# LED-Driver-Sheet.net
KiCad netlist of a schematic drawn in Altium Designer
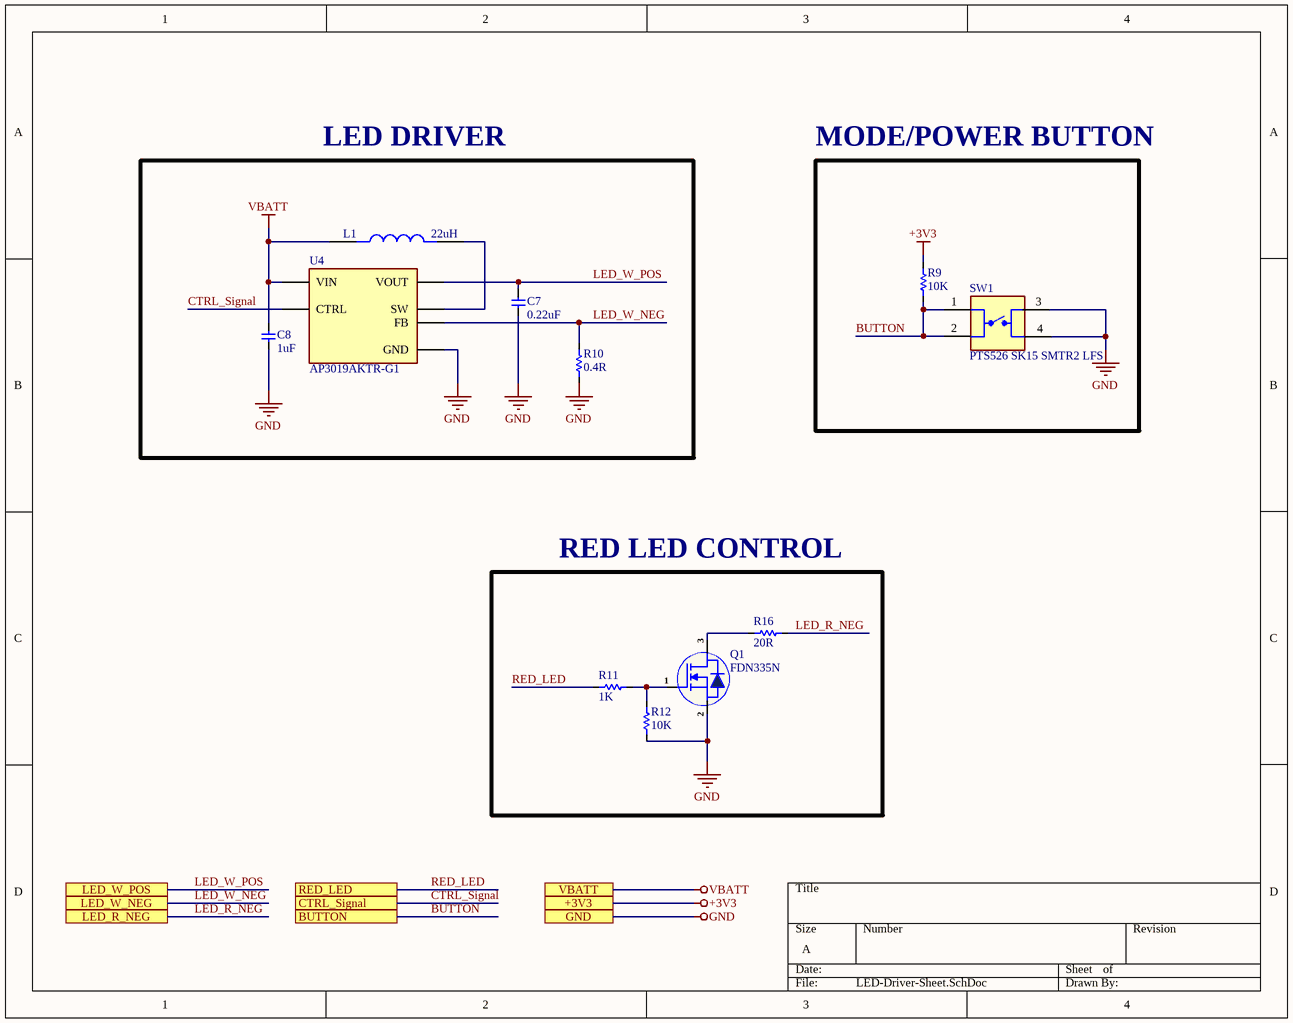
[diagram p0: LED-Driver-Sheet.SchDoc]

(export (version "E")
  (design (tool "Eeschema 10.0.6"))
  (components
    (comp (ref "C7")
      (value "0.22uF")
      (footprint "Cap-0402")
      (description "0.22 µF ±10% 25V Ceramic Capacitor X5R 0402 (1005 Metric)")
      (fields
        (field (name "MANUFACTURER") "YAGEO")
        (field (name "MANUFACTURER PART NUMBER") "CC0402KRX5R8BB224")
      )
      (libsource (lib "LED-Driver-Library") (part "CC0402KRX5R8BB224"))
    )
    (comp (ref "C8")
      (value "1uF")
      (footprint "Cap-0402")
      (description "1 µF ±20% 6.3V Ceramic Capacitor X5R 0201 (0603 Metric)")
      (fields
        (field (name "MANUFACTURER") "Murata Electronics")
        (field (name "MANUFACTURER PART NUMBER") "GRM033R60J105MEA2D")
      )
      (libsource (lib "LED-Driver-Library") (part "GRM033R60J105MEA2D"))
    )
    (comp (ref "L1")
      (value "22uH")
      (footprint "IND_1235AS-H-220M=P3")
      (description "Inductor Power Shielded Wirewound 22uH 20% 100KHz Ferrite 1A 0.306Ohm DCR 1818 T/R")
      (fields
        (field (name "MANUFACTURER") "Murata Electronics")
        (field (name "MANUFACTURER PART NUMBER") "1235AS-H-220M=P3")
      )
      (libsource (lib "LED-Driver-Library") (part "1235AS-H-220M=P3"))
    )
    (comp (ref "Q1")
      (value "FDN335N")
      (footprint "SOT-23")
      (description "SOT-23 MOSFETs ROHS")
      (fields (field (name "MANUFACTURER") "onsemi") (field (name "DIGIKEY PART NUMBER") "FDN335NDKR-ND"))
      (libsource (lib "LED-Driver-Library") (part "FDN335N"))
    )
    (comp (ref "R9")
      (value "10K")
      (footprint "Res-0402")
      (description "10 kOhms ±1% 0.063W, 1/16W Chip Resistor 0402 (1005 Metric) Moisture Resistant Thick Film")
      (fields
        (field (name "MANUFACTURER") "YAGEO")
        (field (name "MANUFACTURER PART NUMBER") "RC0402FR-0710KL")
      )
      (libsource (lib "LED-Driver-Library") (part "RC0603FR-0710KL"))
    )
    (comp (ref "R10")
      (value "0.4R")
      (footprint "Res-1206")
      (fields
        (field (name "MANUFACTURER") "YAGEO")
        (field (name "MANUFACTURER PART NUMBER") "RL1206FR-070R4L")
        (field (name "DIGIKEY PART NUMBER") "311-.4LWDKR-ND")
      )
      (libsource (lib "LED-Driver-Library") (part "RL1206FR-070R4L"))
    )
    (comp (ref "R11")
      (value "1K")
      (footprint "Res-0402")
      (description "1 kOhms ±1% 0.063W, 1/16W Chip Resistor 0402 (1005 Metric) Moisture Resistant Thick Film")
      (fields
        (field (name "MANUFACTURER") "YAGEO")
        (field (name "MANUFACTURER PART NUMBER") "RC0402FR-071KL")
      )
      (libsource (lib "LED-Driver-Library") (part "RC0402FR-071KL"))
    )
    (comp (ref "R12")
      (value "10K")
      (footprint "Res-0402")
      (description "10 kOhms ±1% 0.063W, 1/16W Chip Resistor 0402 (1005 Metric) Moisture Resistant Thick Film")
      (fields
        (field (name "MANUFACTURER") "YAGEO")
        (field (name "MANUFACTURER PART NUMBER") "RC0402FR-0710KL")
      )
      (libsource (lib "LED-Driver-Library") (part "RC0603FR-0710KL"))
    )
    (comp (ref "R16")
      (value "20R")
      (footprint "RESC1005X40N")
      (fields
        (field (name "MANUFACTURER") "Vishay Dale")
        (field (name "MANUFACTURER PART NUMBER") "RCS040220R0FKED")
        (field (name "DIGIKEY PART NUMBER") "541-RCS040220R0FKEDDKR-ND")
      )
      (libsource (lib "LED-Driver-Library") (part "RCS040220R0FKED"))
    )
    (comp (ref "SW1")
      (value "PTS526 SK15 SMTR2 LFS")
      (footprint "PTS525SM15SMTR2LFS")
      (description "Tactile Switch SPST-NO Top Actuated Surface Mount")
      (fields
        (field (name "MANUFACTURER") "TE Connectivity ALCOSWITCH Switches")
        (field (name "MANUFACTURER PART NUMBER") "MCSLPT4644B1PHTR")
      )
      (libsource (lib "LED-Driver-Library") (part "MCSLPT4644B1PHTR"))
    )
    (comp (ref "U4")
      (value "AP3019AKTR-G1")
      (footprint "AP3019AKTR-G1")
      (description "LED Driver IC 1 Output DC DC Regulator Step-Up (Boost) PWM Dimming 550mA (Switch) SOT-23-6")
      (fields
        (field (name "MANUFACTURER") "Diodes Incorporated")
        (field (name "DIGIKEY PART NUMBER") "AP3019AKTR-G1DIDKR-ND")
      )
      (libsource (lib "LED-Driver-Library") (part "AP3019AKTR-G1"))
    )
  )
  (nets
    (net (code "1") (name "+3V3") (class "Default")
      (node (ref "R9") (pin "1") (pinfunction "1_1") (pintype "passive"))
    )
    (net (code "2") (name "/BUTTON") (class "Default")
      (node (ref "R9") (pin "2") (pinfunction "2_2") (pintype "passive"))
      (node (ref "SW1") (pin "1") (pinfunction "1_1") (pintype "passive"))
      (node (ref "SW1") (pin "2") (pinfunction "2_2") (pintype "passive"))
    )
    (net (code "3") (name "/CTRL_Signal") (class "Default")
      (node (ref "U4") (pin "4") (pinfunction "CTRL_4") (pintype "passive"))
    )
    (net (code "4") (name "/LED_R_NEG") (class "Default")
      (node (ref "R16") (pin "2") (pinfunction "2_2") (pintype "passive"))
    )
    (net (code "5") (name "/LED_W_NEG") (class "Default")
      (node (ref "R10") (pin "2") (pinfunction "2_2") (pintype "passive"))
      (node (ref "U4") (pin "3") (pinfunction "FB_3") (pintype "passive"))
    )
    (net (code "6") (name "/LED_W_POS") (class "Default")
      (node (ref "C7") (pin "2") (pinfunction "2_2") (pintype "passive"))
      (node (ref "U4") (pin "5") (pinfunction "VOUT_5") (pintype "passive"))
    )
    (net (code "7") (name "/RED_LED") (class "Default")
      (node (ref "R11") (pin "1") (pinfunction "1_1") (pintype "passive"))
    )
    (net (code "8") (name "GND") (class "Default")
      (node (ref "C7") (pin "1") (pinfunction "1_1") (pintype "passive"))
      (node (ref "C8") (pin "1") (pinfunction "1_1") (pintype "passive"))
      (node (ref "Q1") (pin "2") (pinfunction "S_2") (pintype "passive"))
      (node (ref "R10") (pin "1") (pinfunction "1_1") (pintype "passive"))
      (node (ref "R12") (pin "2") (pinfunction "2_2") (pintype "passive"))
      (node (ref "SW1") (pin "3") (pinfunction "3_3") (pintype "passive"))
      (node (ref "SW1") (pin "4") (pinfunction "4_4") (pintype "passive"))
      (node (ref "U4") (pin "2") (pinfunction "GND_2") (pintype "passive"))
    )
    (net (code "9") (name "Net-(Q1-D)") (class "Default")
      (node (ref "Q1") (pin "3") (pinfunction "D_3") (pintype "passive"))
      (node (ref "R16") (pin "1") (pinfunction "1_1") (pintype "passive"))
    )
    (net (code "10") (name "Net-(Q1-G)") (class "Default")
      (node (ref "Q1") (pin "1") (pinfunction "G_1") (pintype "passive"))
      (node (ref "R11") (pin "2") (pinfunction "2_2") (pintype "passive"))
      (node (ref "R12") (pin "1") (pinfunction "1_1") (pintype "passive"))
    )
    (net (code "11") (name "Net-(U4-SW)") (class "Default")
      (node (ref "L1") (pin "2") (pinfunction "2_2") (pintype "passive"))
      (node (ref "U4") (pin "1") (pinfunction "SW_1") (pintype "passive"))
    )
    (net (code "12") (name "VBATT") (class "Default")
      (node (ref "C8") (pin "2") (pinfunction "2_2") (pintype "passive"))
      (node (ref "L1") (pin "1") (pinfunction "1_1") (pintype "passive"))
      (node (ref "U4") (pin "6") (pinfunction "VIN_6") (pintype "passive"))
    )
  )
)
